# 14-StepMotor.net
KiCad netlist of a schematic drawn in Altium Designer
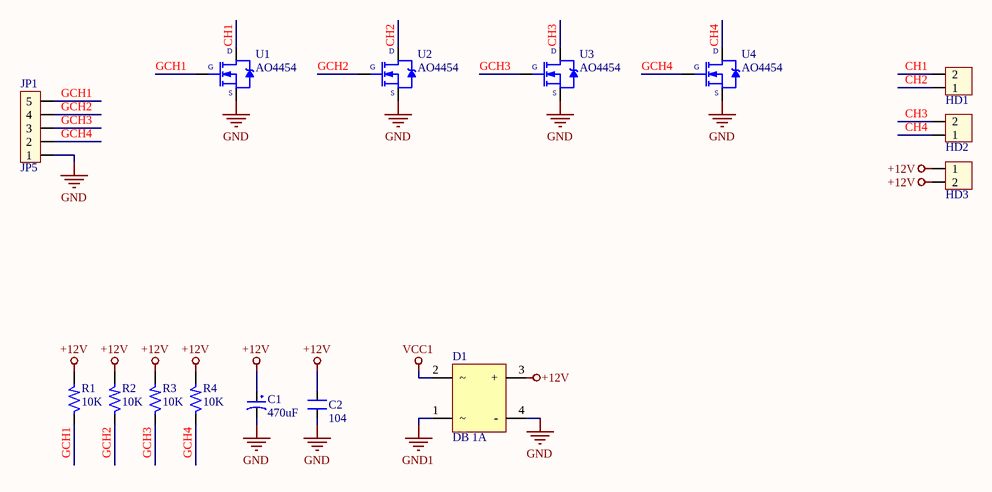
[diagram p0: 14-StepMotor.SchDoc]

(export (version "E")
  (design (tool "Eeschema 10.0.6"))
  (components
    (comp (ref "C1")
      (value "470uF")
      (footprint "C-ALU-D6.5")
      (description "Cap P  0,1uF < 22uF , 16 - 50V")
      (libsource (lib "PART") (part "CP1"))
    )
    (comp (ref "C2")
      (value "104")
      (footprint "C-0805")
      (fields (field (name "DESIGNED BY") "VanDungEvn"))
      (libsource (lib "syhaunguyen") (part "CN"))
    )
    (comp (ref "D1")
      (value "DB 1A")
      (footprint "D-DB-1A-SMD")
      (libsource (lib "doAnTotNghiep2017Lib") (part "DB"))
    )
    (comp (ref "HD1")
      (value "CH1")
      (footprint "TER-KF301-2")
      (description "Header 2 (Green)")
      (libsource (lib "syhaunguyen") (part "Hed2"))
    )
    (comp (ref "HD2")
      (value "CH1")
      (footprint "TER-KF301-2")
      (description "Header 2 (Green)")
      (libsource (lib "syhaunguyen") (part "Hed2"))
    )
    (comp (ref "HD3")
      (value "CH1")
      (footprint "TER-KF301-2")
      (description "Header 2 (Green)")
      (libsource (lib "") (part "Hed2_1"))
    )
    (comp (ref "JP1") (value "JP5") (footprint "JP5") (libsource (lib "syhaunguyen") (part "JP5")))
    (comp (ref "R1")
      (value "10K")
      (footprint "R-0805")
      (description "Resistor 1/4W")
      (libsource (lib "syhaunguyen") (part "R"))
    )
    (comp (ref "R2")
      (value "10K")
      (footprint "R-0805")
      (description "Resistor 1/4W")
      (libsource (lib "syhaunguyen") (part "R"))
    )
    (comp (ref "R3")
      (value "10K")
      (footprint "R-0805")
      (description "Resistor 1/4W")
      (libsource (lib "syhaunguyen") (part "R"))
    )
    (comp (ref "R4")
      (value "10K")
      (footprint "R-0805")
      (description "Resistor 1/4W")
      (libsource (lib "syhaunguyen") (part "R"))
    )
    (comp (ref "U1")
      (value "AO4454")
      (footprint "TO-252")
      (libsource (lib "doAnTotNghiep2017Lib") (part "AO4454"))
    )
    (comp (ref "U2")
      (value "AO4454")
      (footprint "TO-252")
      (libsource (lib "doAnTotNghiep2017Lib") (part "AO4454"))
    )
    (comp (ref "U3")
      (value "AO4454")
      (footprint "TO-252")
      (libsource (lib "doAnTotNghiep2017Lib") (part "AO4454"))
    )
    (comp (ref "U4")
      (value "AO4454")
      (footprint "TO-252")
      (libsource (lib "doAnTotNghiep2017Lib") (part "AO4454"))
    )
  )
  (nets
    (net (code "1") (name "+12V") (class "Default")
      (node (ref "C1") (pin "1") (pinfunction "1_1") (pintype "passive"))
      (node (ref "C2") (pin "2") (pinfunction "2_2") (pintype "passive"))
      (node (ref "D1") (pin "3") (pinfunction "+_3") (pintype "passive"))
      (node (ref "HD3") (pin "1") (pinfunction "1_1") (pintype "passive"))
      (node (ref "HD3") (pin "2") (pinfunction "2_2") (pintype "passive"))
      (node (ref "R1") (pin "2") (pinfunction "2_2") (pintype "passive"))
      (node (ref "R2") (pin "2") (pinfunction "2_2") (pintype "passive"))
      (node (ref "R3") (pin "2") (pinfunction "2_2") (pintype "passive"))
      (node (ref "R4") (pin "2") (pinfunction "2_2") (pintype "passive"))
    )
    (net (code "2") (name "/CH1") (class "Default")
      (node (ref "HD1") (pin "2") (pinfunction "2_2") (pintype "passive"))
      (node (ref "U1") (pin "2") (pinfunction "D_2") (pintype "passive"))
    )
    (net (code "3") (name "/CH2") (class "Default")
      (node (ref "HD1") (pin "1") (pinfunction "1_1") (pintype "passive"))
      (node (ref "U2") (pin "2") (pinfunction "D_2") (pintype "passive"))
    )
    (net (code "4") (name "/CH3") (class "Default")
      (node (ref "HD2") (pin "2") (pinfunction "2_2") (pintype "passive"))
      (node (ref "U3") (pin "2") (pinfunction "D_2") (pintype "passive"))
    )
    (net (code "5") (name "/CH4") (class "Default")
      (node (ref "HD2") (pin "1") (pinfunction "1_1") (pintype "passive"))
      (node (ref "U4") (pin "2") (pinfunction "D_2") (pintype "passive"))
    )
    (net (code "6") (name "/GCH1") (class "Default")
      (node (ref "JP1") (pin "5") (pinfunction "5_5") (pintype "passive"))
      (node (ref "R1") (pin "1") (pinfunction "1_1") (pintype "passive"))
      (node (ref "U1") (pin "1") (pinfunction "G_1") (pintype "passive"))
    )
    (net (code "7") (name "/GCH2") (class "Default")
      (node (ref "JP1") (pin "4") (pinfunction "4_4") (pintype "passive"))
      (node (ref "R2") (pin "1") (pinfunction "1_1") (pintype "passive"))
      (node (ref "U2") (pin "1") (pinfunction "G_1") (pintype "passive"))
    )
    (net (code "8") (name "/GCH3") (class "Default")
      (node (ref "JP1") (pin "3") (pinfunction "3_3") (pintype "passive"))
      (node (ref "R3") (pin "1") (pinfunction "1_1") (pintype "passive"))
      (node (ref "U3") (pin "1") (pinfunction "G_1") (pintype "passive"))
    )
    (net (code "9") (name "/GCH4") (class "Default")
      (node (ref "JP1") (pin "2") (pinfunction "2_2") (pintype "passive"))
      (node (ref "R4") (pin "1") (pinfunction "1_1") (pintype "passive"))
      (node (ref "U4") (pin "1") (pinfunction "G_1") (pintype "passive"))
    )
    (net (code "10") (name "GND") (class "Default")
      (node (ref "C1") (pin "2") (pinfunction "2_2") (pintype "passive"))
      (node (ref "C2") (pin "1") (pinfunction "1_1") (pintype "passive"))
      (node (ref "D1") (pin "4") (pinfunction "-_4") (pintype "passive"))
      (node (ref "JP1") (pin "1") (pinfunction "1_1") (pintype "passive"))
      (node (ref "U1") (pin "3") (pinfunction "S_3") (pintype "passive"))
      (node (ref "U2") (pin "3") (pinfunction "S_3") (pintype "passive"))
      (node (ref "U3") (pin "3") (pinfunction "S_3") (pintype "passive"))
      (node (ref "U4") (pin "3") (pinfunction "S_3") (pintype "passive"))
    )
    (net (code "11") (name "GND1") (class "Default")
      (node (ref "D1") (pin "1") (pinfunction "~_1") (pintype "passive"))
    )
    (net (code "12") (name "VCC1") (class "Default")
      (node (ref "D1") (pin "2") (pinfunction "~_2") (pintype "passive"))
    )
  )
)
